# io_board.net
KiCad netlist of a schematic drawn in EAGLE
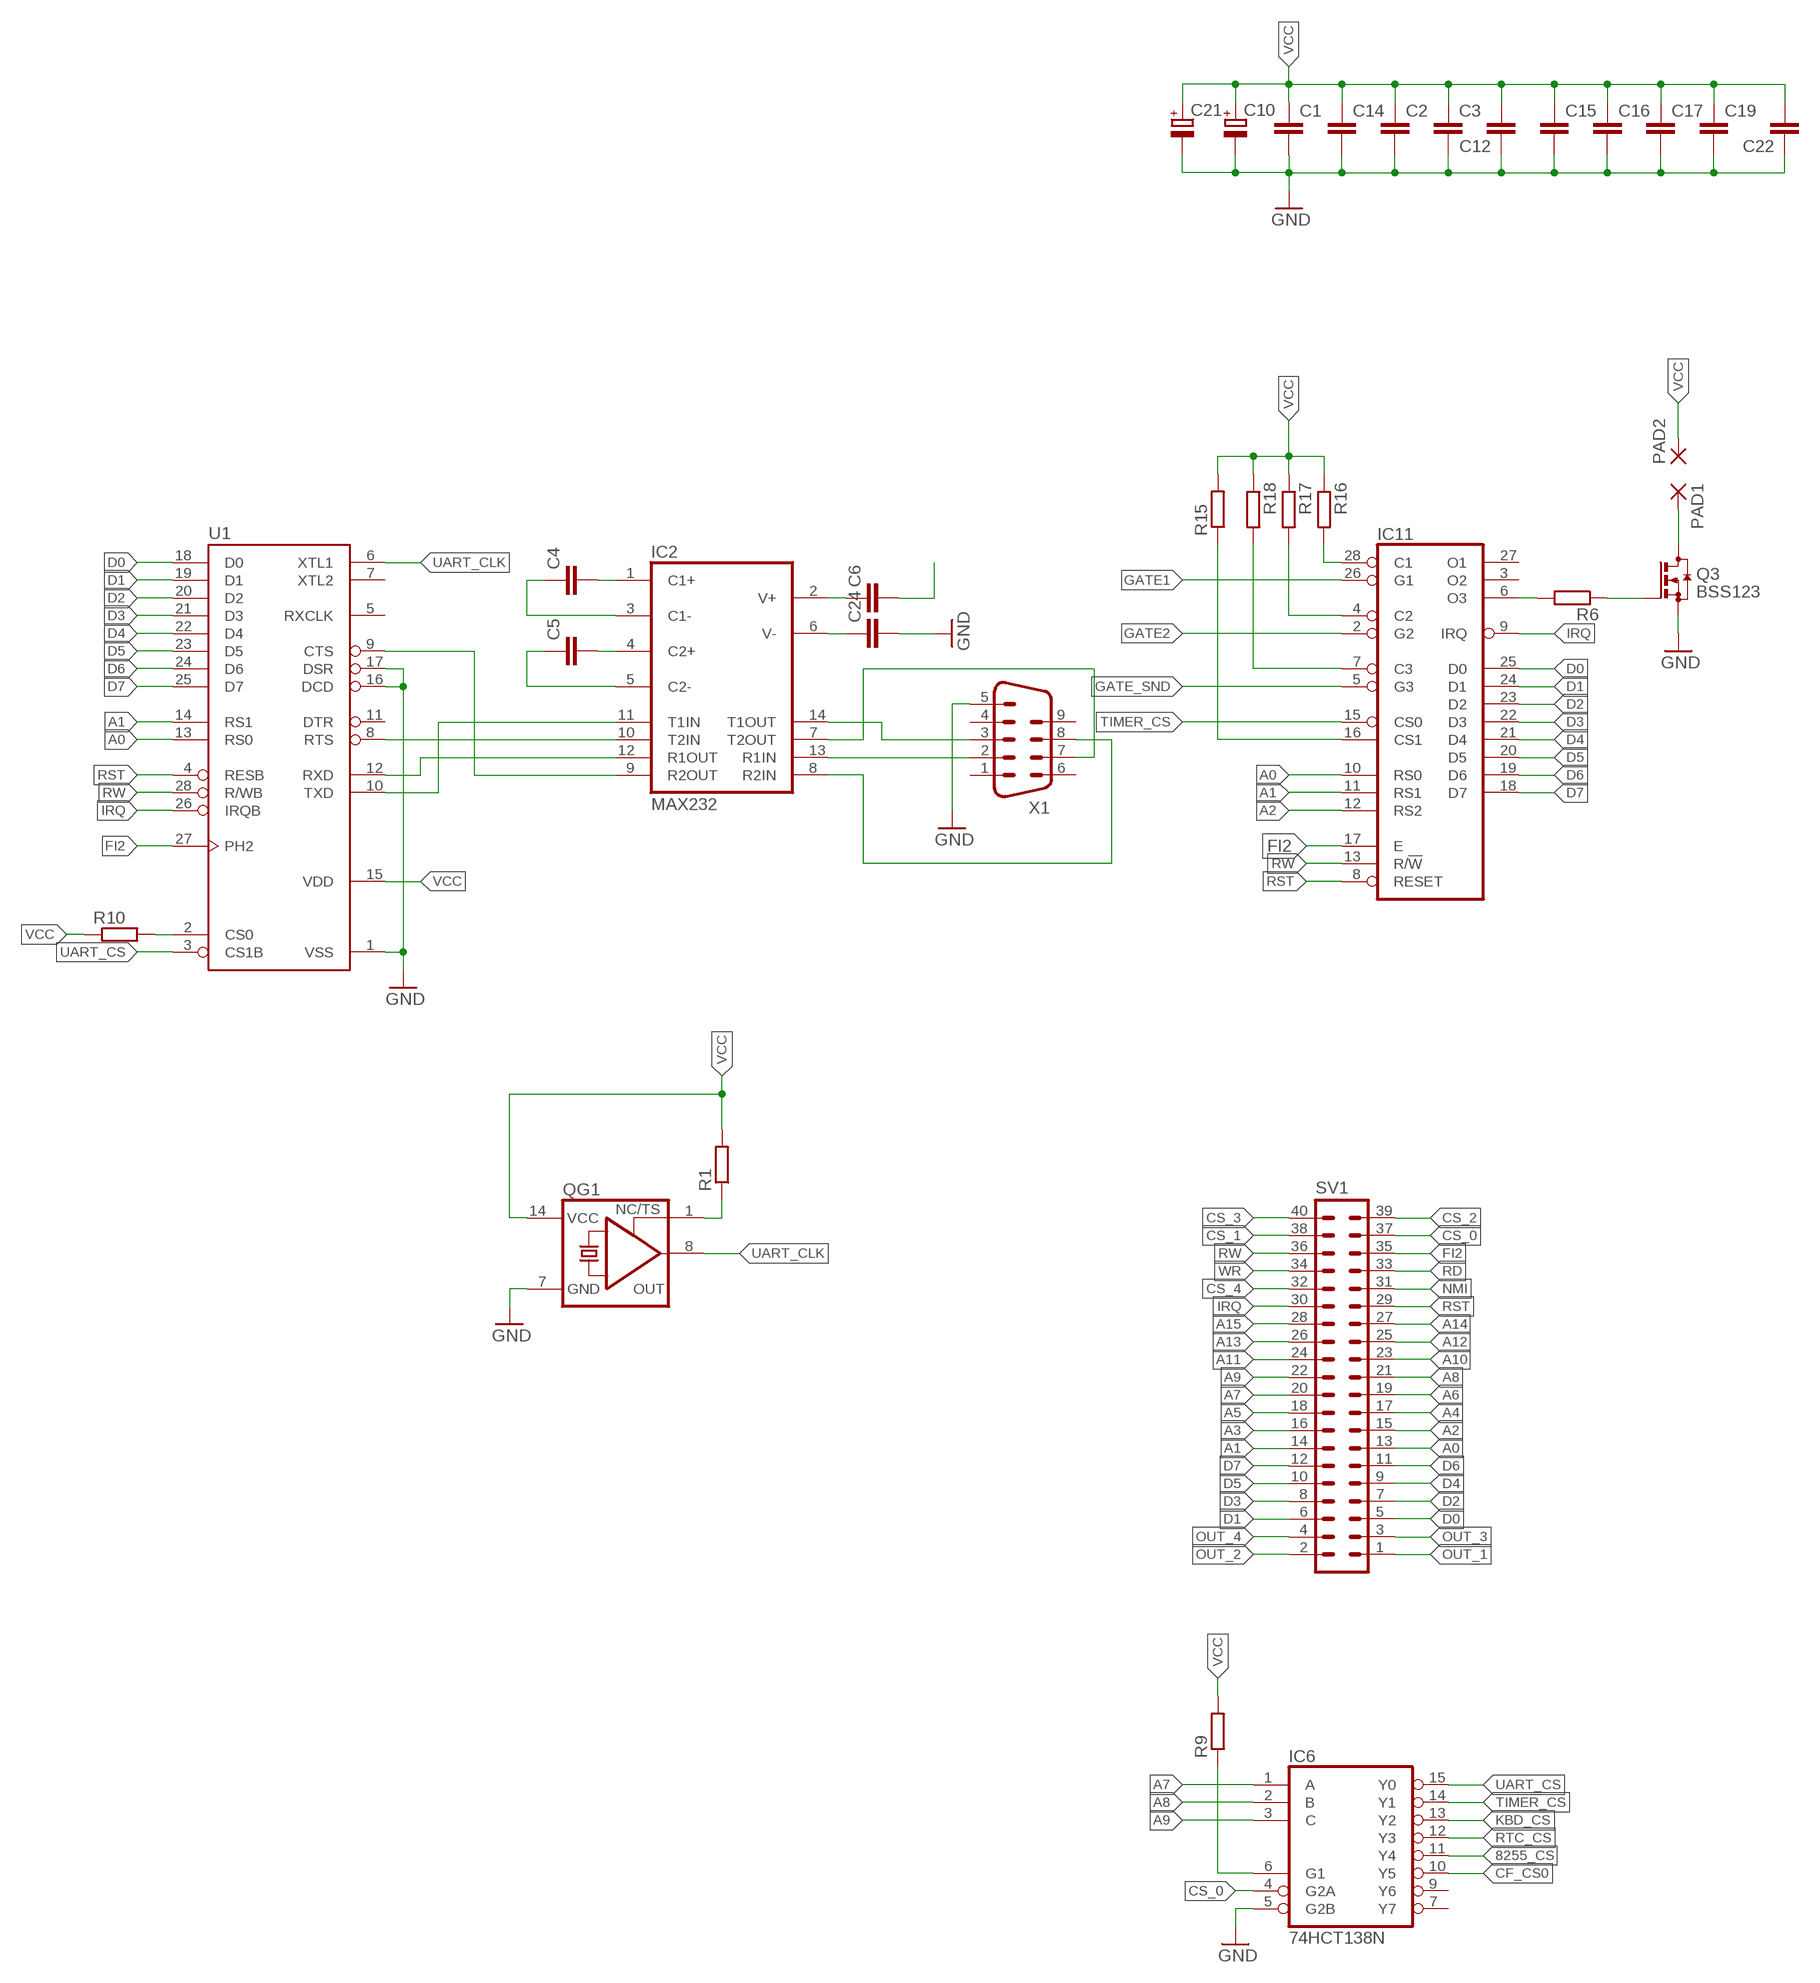
[diagram p0: schematic, sheet 1, part 1 of 2]
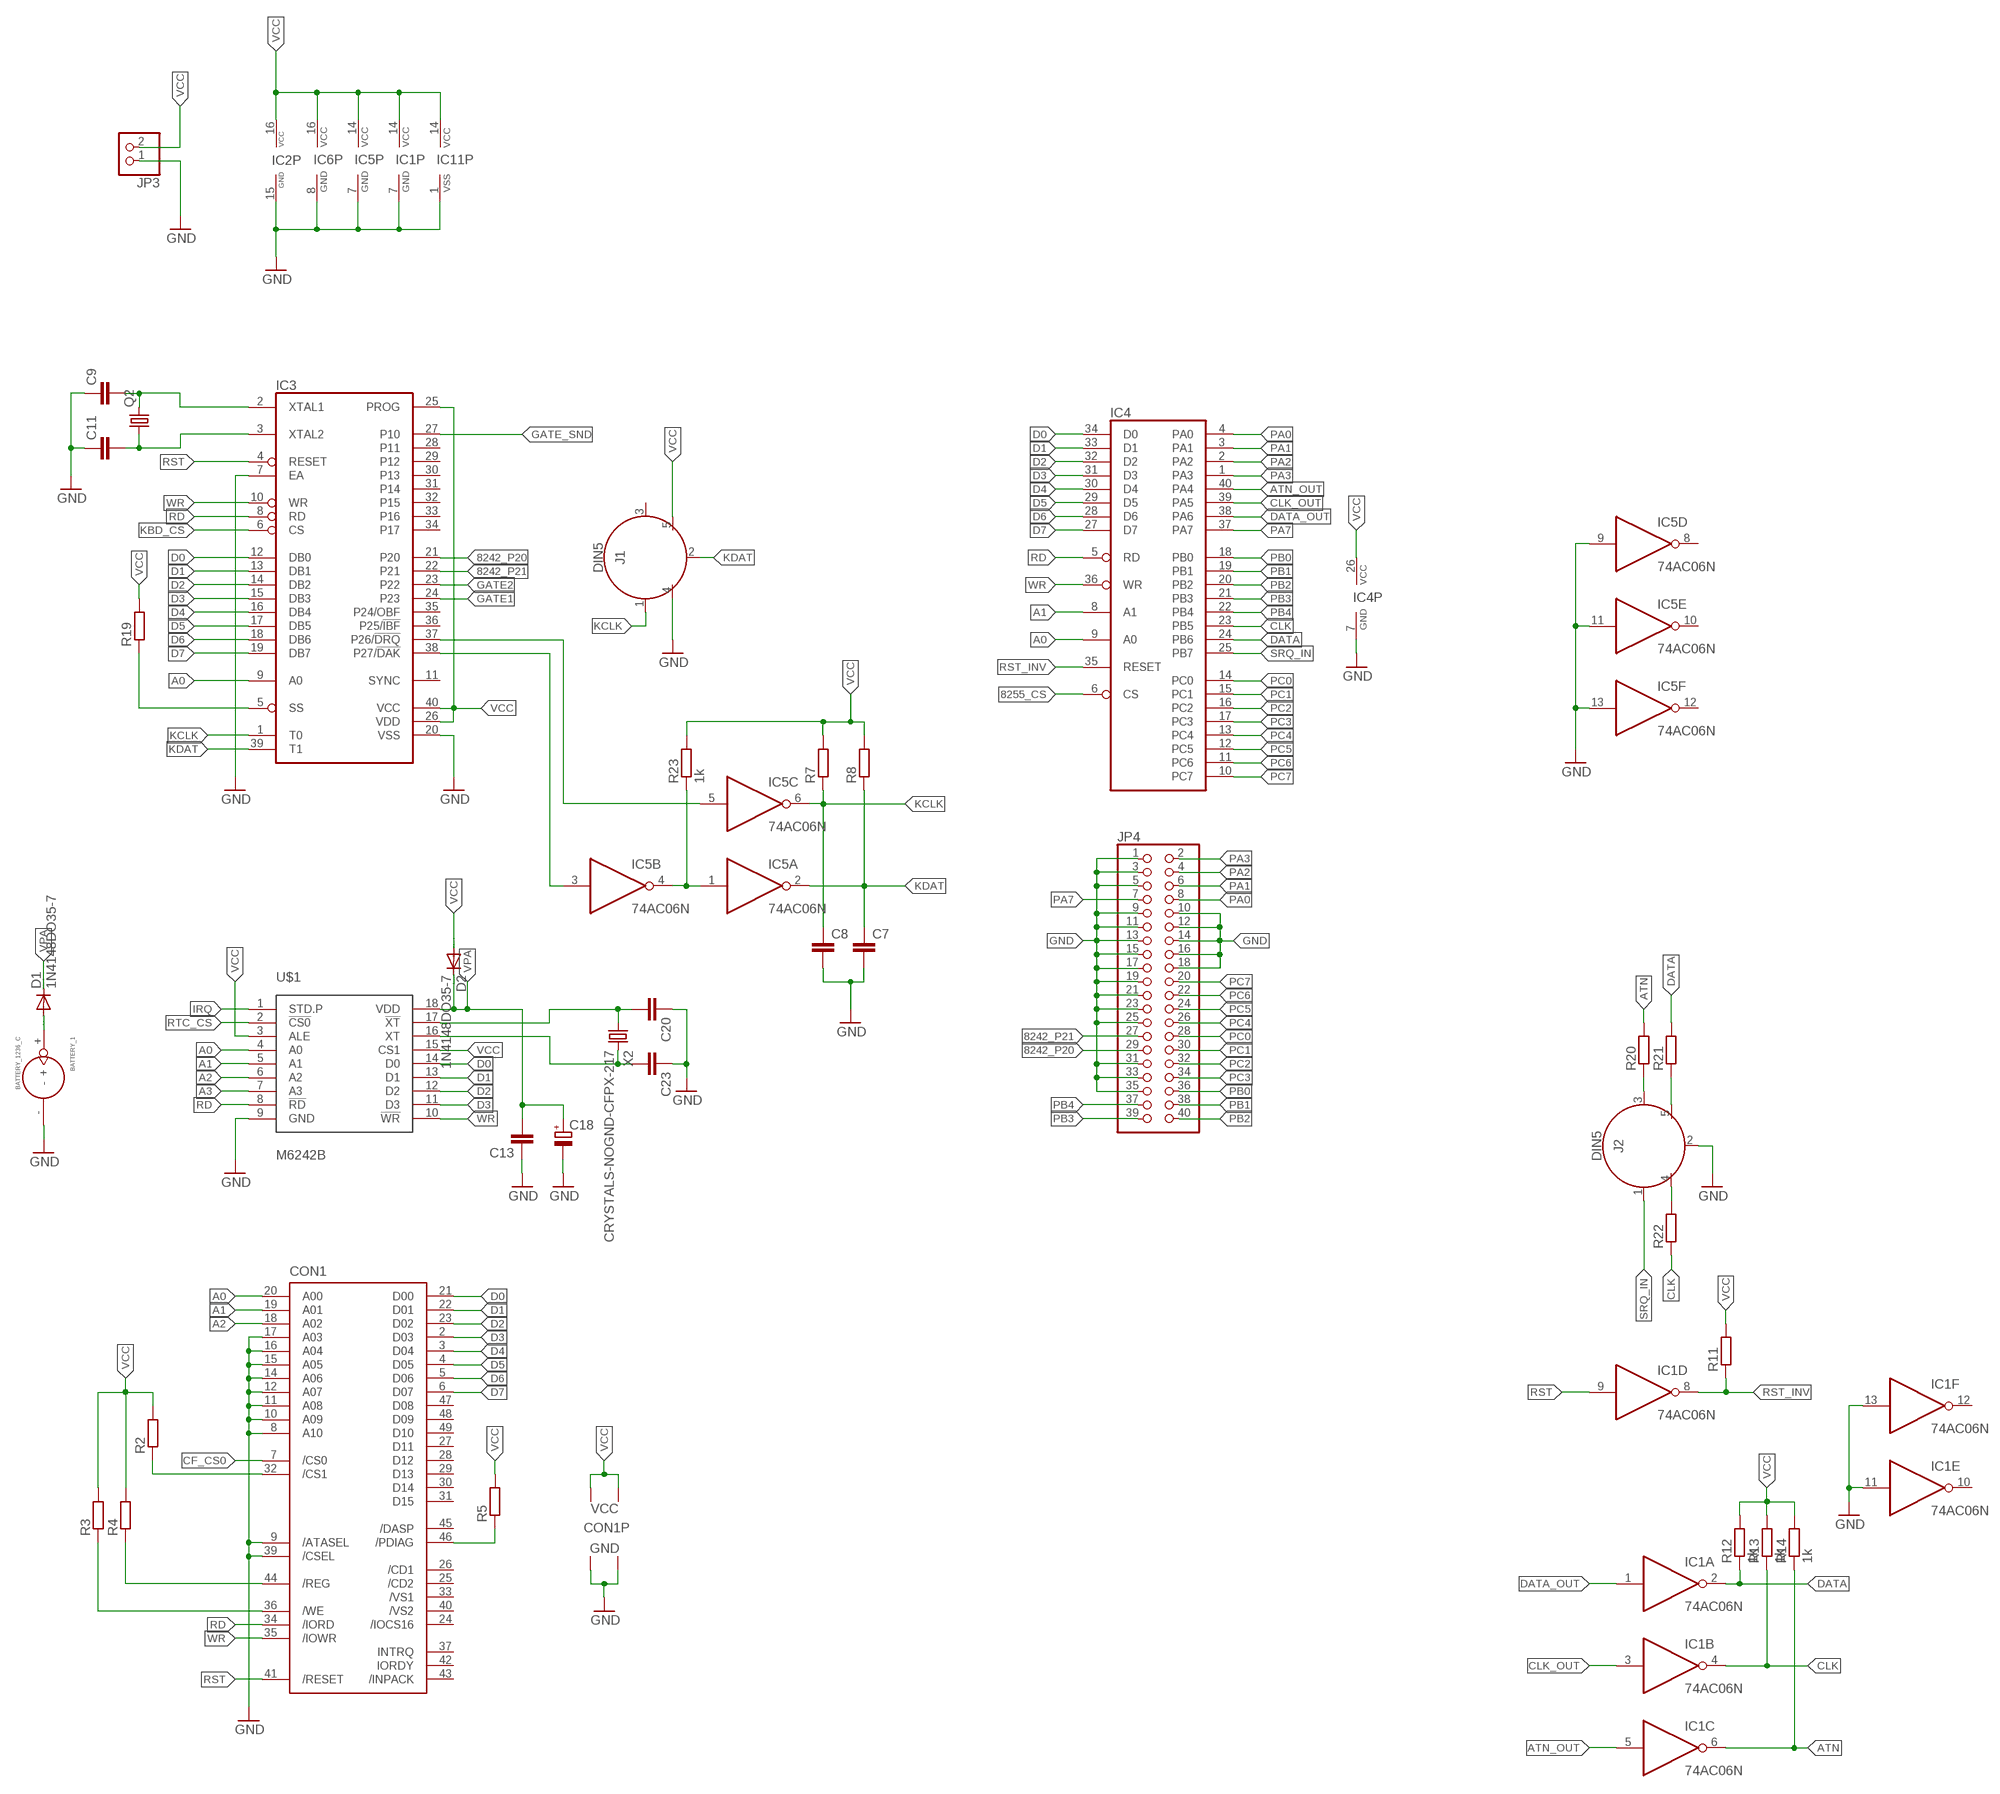
[diagram p1: schematic, sheet 1, part 2 of 2]

(export (version "E")
  (design (tool "Eeschema 10.0.6"))
  (components
    (comp (ref "BATTERY_1")
      (value "BATTERY_1236_C")
      (footprint "eagle-import:BATTERY_1236_C")
      (libsource (lib "eagle-import") (part "BATTERY_1236_C"))
    )
    (comp (ref "C1")
      (value "C-EUC1206")
      (footprint "eagle-import:C1206")
      (libsource (lib "eagle-import") (part "C-EUC1206"))
    )
    (comp (ref "C2")
      (value "C-EUC1206")
      (footprint "eagle-import:C1206")
      (libsource (lib "eagle-import") (part "C-EUC1206"))
    )
    (comp (ref "C3")
      (value "C-EUC1206")
      (footprint "eagle-import:C1206")
      (libsource (lib "eagle-import") (part "C-EUC1206"))
    )
    (comp (ref "C4")
      (value "C-EUC0603")
      (footprint "eagle-import:C0603")
      (libsource (lib "eagle-import") (part "C-EUC0603"))
    )
    (comp (ref "C5")
      (value "C-EUC0603")
      (footprint "eagle-import:C0603")
      (libsource (lib "eagle-import") (part "C-EUC0603"))
    )
    (comp (ref "C6")
      (value "C-EUC0603")
      (footprint "eagle-import:C0603")
      (libsource (lib "eagle-import") (part "C-EUC0603"))
    )
    (comp (ref "C7")
      (value "C-EUC0603")
      (footprint "eagle-import:C0603")
      (libsource (lib "eagle-import") (part "C-EUC0603"))
    )
    (comp (ref "C8")
      (value "C-EUC0603")
      (footprint "eagle-import:C0603")
      (libsource (lib "eagle-import") (part "C-EUC0603"))
    )
    (comp (ref "C9")
      (value "C-EUC0603")
      (footprint "eagle-import:C0603")
      (libsource (lib "eagle-import") (part "C-EUC0603"))
    )
    (comp (ref "C10")
      (value "CPOL-EUE5-10.5")
      (footprint "eagle-import:E5-10,5")
      (libsource (lib "eagle-import") (part "CPOL-EUE5-10.5"))
    )
    (comp (ref "C11")
      (value "C-EUC0603")
      (footprint "eagle-import:C0603")
      (libsource (lib "eagle-import") (part "C-EUC0603"))
    )
    (comp (ref "C12")
      (value "C-EUC0603")
      (footprint "eagle-import:C0603")
      (libsource (lib "eagle-import") (part "C-EUC0603"))
    )
    (comp (ref "C13")
      (value "C-EUC0603")
      (footprint "eagle-import:C0603")
      (libsource (lib "eagle-import") (part "C-EUC0603"))
    )
    (comp (ref "C14")
      (value "C-EUC1206")
      (footprint "eagle-import:C1206")
      (libsource (lib "eagle-import") (part "C-EUC1206"))
    )
    (comp (ref "C15")
      (value "C-EUC1206")
      (footprint "eagle-import:C1206")
      (libsource (lib "eagle-import") (part "C-EUC1206"))
    )
    (comp (ref "C16")
      (value "C-EUC1206")
      (footprint "eagle-import:C1206")
      (libsource (lib "eagle-import") (part "C-EUC1206"))
    )
    (comp (ref "C17")
      (value "C-EUC1206")
      (footprint "eagle-import:C1206")
      (libsource (lib "eagle-import") (part "C-EUC1206"))
    )
    (comp (ref "C18")
      (value "CPOL-EUSMCB")
      (footprint "eagle-import:SMC_B")
      (libsource (lib "eagle-import") (part "CPOL-EUSMCB"))
    )
    (comp (ref "C19")
      (value "C-EUC0603")
      (footprint "eagle-import:C0603")
      (libsource (lib "eagle-import") (part "C-EUC0603"))
    )
    (comp (ref "C20")
      (value "C-EUC0603")
      (footprint "eagle-import:C0603")
      (libsource (lib "eagle-import") (part "C-EUC0603"))
    )
    (comp (ref "C21")
      (value "CPOL-EUSMCB")
      (footprint "eagle-import:SMC_B")
      (libsource (lib "eagle-import") (part "CPOL-EUSMCB"))
    )
    (comp (ref "C22")
      (value "C-EUC0603")
      (footprint "eagle-import:C0603")
      (libsource (lib "eagle-import") (part "C-EUC0603"))
    )
    (comp (ref "C23")
      (value "C-EUC0603")
      (footprint "eagle-import:C0603")
      (libsource (lib "eagle-import") (part "C-EUC0603"))
    )
    (comp (ref "C24")
      (value "C-EUC0603")
      (footprint "eagle-import:C0603")
      (libsource (lib "eagle-import") (part "C-EUC0603"))
    )
    (comp (ref "CON1")
      (value "CF-CARD-IDE_MODE")
      (footprint "eagle-import:MI20-50PD-SF")
      (libsource (lib "eagle-import") (part "CF-CARD-IDE_MODE"))
    )
    (comp (ref "D1")
      (value "1N4148DO35-7")
      (footprint "eagle-import:DO35-7")
      (libsource (lib "eagle-import") (part "1N4148DO35-7"))
    )
    (comp (ref "D2")
      (value "1N4148DO35-7")
      (footprint "eagle-import:DO35-7")
      (libsource (lib "eagle-import") (part "1N4148DO35-7"))
    )
    (comp (ref "IC1")
      (value "74AC06N")
      (footprint "eagle-import:DIL14")
      (libsource (lib "eagle-import") (part "7406NAC"))
    )
    (comp (ref "IC2")
      (value "MAX232")
      (footprint "eagle-import:DIL16")
      (fields (field (name "MF") "MAXIM") (field (name "MPN") "MAX232ACPE+"))
      (libsource (lib "eagle-import") (part "MAX232"))
    )
    (comp (ref "IC3")
      (value "UPI-8042AH")
      (footprint "eagle-import:DIL40")
      (libsource (lib "eagle-import") (part "UPI-8042AH"))
    )
    (comp (ref "IC4")
      (value "8255A")
      (footprint "eagle-import:DIL40")
      (libsource (lib "eagle-import") (part "8255A"))
    )
    (comp (ref "IC5")
      (value "74AC06N")
      (footprint "eagle-import:DIL14")
      (libsource (lib "eagle-import") (part "7406NAC"))
    )
    (comp (ref "IC6")
      (value "74HCT138N")
      (footprint "eagle-import:DIL16")
      (libsource (lib "eagle-import") (part "74138NHCT"))
    )
    (comp (ref "IC11")
      (value "6840")
      (footprint "eagle-import:DIL28")
      (libsource (lib "eagle-import") (part "6840"))
    )
    (comp (ref "J1")
      (value "DIN5")
      (footprint "eagle-import:DIN5-RA-PTH")
      (libsource (lib "eagle-import") (part "DIN5"))
    )
    (comp (ref "J2")
      (value "DIN5")
      (footprint "eagle-import:DIN5-RA-PTH")
      (libsource (lib "eagle-import") (part "DIN5"))
    )
    (comp (ref "JP3")
      (value "PINHD-1X2/90")
      (footprint "eagle-import:1X02_90")
      (libsource (lib "eagle-import") (part "PINHD-1X2/90"))
    )
    (comp (ref "JP4")
      (value "PINHD-2X20")
      (footprint "eagle-import:2X20")
      (libsource (lib "eagle-import") (part "PINHD-2X20"))
    )
    (comp (ref "PAD1")
      (value "2,15/1,0")
      (footprint "eagle-import:2,15_1,0")
      (libsource (lib "eagle-import") (part "2,15/1,0"))
    )
    (comp (ref "PAD2")
      (value "2,15/1,0")
      (footprint "eagle-import:2,15_1,0")
      (libsource (lib "eagle-import") (part "2,15/1,0"))
    )
    (comp (ref "Q2")
      (value "CRYSTALHC49S")
      (footprint "eagle-import:HC49_S")
      (libsource (lib "eagle-import") (part "CRYSTALHC49S"))
    )
    (comp (ref "Q3")
      (value "BSS123")
      (footprint "eagle-import:SOT23")
      (libsource (lib "eagle-import") (part "BSS123"))
    )
    (comp (ref "QG1")
      (value "XO-14")
      (footprint "eagle-import:DIL14S")
      (libsource (lib "eagle-import") (part "XO-14"))
    )
    (comp (ref "R1")
      (value "R-EU_R1206")
      (footprint "eagle-import:R1206")
      (libsource (lib "eagle-import") (part "R-EU_R1206"))
    )
    (comp (ref "R2")
      (value "R-EU_R0603")
      (footprint "eagle-import:R0603")
      (libsource (lib "eagle-import") (part "R-EU_R0603"))
    )
    (comp (ref "R3")
      (value "R-EU_R0603")
      (footprint "eagle-import:R0603")
      (libsource (lib "eagle-import") (part "R-EU_R0603"))
    )
    (comp (ref "R4")
      (value "R-EU_R0603")
      (footprint "eagle-import:R0603")
      (libsource (lib "eagle-import") (part "R-EU_R0603"))
    )
    (comp (ref "R5")
      (value "R-EU_R0603")
      (footprint "eagle-import:R0603")
      (libsource (lib "eagle-import") (part "R-EU_R0603"))
    )
    (comp (ref "R6")
      (value "R-EU_R0603")
      (footprint "eagle-import:R0603")
      (libsource (lib "eagle-import") (part "R-EU_R0603"))
    )
    (comp (ref "R7")
      (value "R-EU_R0603")
      (footprint "eagle-import:R0603")
      (libsource (lib "eagle-import") (part "R-EU_R0603"))
    )
    (comp (ref "R8")
      (value "R-EU_R0603")
      (footprint "eagle-import:R0603")
      (libsource (lib "eagle-import") (part "R-EU_R0603"))
    )
    (comp (ref "R9")
      (value "R-EU_R1206")
      (footprint "eagle-import:R1206")
      (libsource (lib "eagle-import") (part "R-EU_R1206"))
    )
    (comp (ref "R10")
      (value "R-EU_R0603")
      (footprint "eagle-import:R0603")
      (libsource (lib "eagle-import") (part "R-EU_R0603"))
    )
    (comp (ref "R11")
      (value "R-EU_R0603")
      (footprint "eagle-import:R0603")
      (libsource (lib "eagle-import") (part "R-EU_R0603"))
    )
    (comp (ref "R12")
      (value "1k")
      (footprint "eagle-import:0204_7")
      (libsource (lib "eagle-import") (part "R-EU_0204/7"))
    )
    (comp (ref "R13")
      (value "1k")
      (footprint "eagle-import:0204_5")
      (libsource (lib "eagle-import") (part "R-EU_0204/5"))
    )
    (comp (ref "R14")
      (value "1k")
      (footprint "eagle-import:0204_7")
      (libsource (lib "eagle-import") (part "R-EU_0204/7"))
    )
    (comp (ref "R15")
      (value "R-EU_R0603")
      (footprint "eagle-import:R0603")
      (libsource (lib "eagle-import") (part "R-EU_R0603"))
    )
    (comp (ref "R16")
      (value "R-EU_0204/5")
      (footprint "eagle-import:0204_5")
      (libsource (lib "eagle-import") (part "R-EU_0204/5"))
    )
    (comp (ref "R17")
      (value "R-EU_R0603")
      (footprint "eagle-import:R0603")
      (libsource (lib "eagle-import") (part "R-EU_R0603"))
    )
    (comp (ref "R18")
      (value "R-EU_R0603")
      (footprint "eagle-import:R0603")
      (libsource (lib "eagle-import") (part "R-EU_R0603"))
    )
    (comp (ref "R19")
      (value "R-EU_0204/5")
      (footprint "eagle-import:0204_5")
      (libsource (lib "eagle-import") (part "R-EU_0204/5"))
    )
    (comp (ref "R20")
      (value "R-EU_R0805")
      (footprint "eagle-import:R0805")
      (libsource (lib "eagle-import") (part "R-EU_R0805"))
    )
    (comp (ref "R21")
      (value "R-EU_R0805")
      (footprint "eagle-import:R0805")
      (libsource (lib "eagle-import") (part "R-EU_R0805"))
    )
    (comp (ref "R22")
      (value "R-EU_R0805")
      (footprint "eagle-import:R0805")
      (libsource (lib "eagle-import") (part "R-EU_R0805"))
    )
    (comp (ref "R23")
      (value "1k")
      (footprint "eagle-import:0204_7")
      (libsource (lib "eagle-import") (part "R-EU_0204/7"))
    )
    (comp (ref "SV1")
      (value "ML40L")
      (footprint "eagle-import:ML40L")
      (libsource (lib "eagle-import") (part "ML40L"))
    )
    (comp (ref "U$1")
      (value "M6242B")
      (footprint "eagle-import:DIL18")
      (libsource (lib "eagle-import") (part "M6242B"))
    )
    (comp (ref "U1")
      (value "G65SC51P")
      (footprint "eagle-import:DIP-28")
      (libsource (lib "eagle-import") (part "G65SC51P"))
    )
    (comp (ref "X1")
      (value "M09HP")
      (footprint "eagle-import:M09HP")
      (libsource (lib "eagle-import") (part "M09HP"))
    )
    (comp (ref "X2")
      (value "CRYSTALS-NOGND-CFPX-217")
      (footprint "eagle-import:3.2X1.5-2-PAD")
      (libsource (lib "eagle-import") (part "CRYSTALS-NOGND-CFPX-217"))
    )
  )
  (nets
    (net (code "1") (name "8242_P20") (class "Default")
      (node (ref "IC3") (pin "21") (pinfunction "P20_21") (pintype "bidirectional"))
      (node (ref "JP4") (pin "29") (pinfunction "29_29") (pintype "passive"))
    )
    (net (code "2") (name "8242_P21") (class "Default")
      (node (ref "IC3") (pin "22") (pinfunction "P21_22") (pintype "bidirectional"))
      (node (ref "JP4") (pin "27") (pinfunction "27_27") (pintype "passive"))
    )
    (net (code "3") (name "8255_CS") (class "Default")
      (node (ref "IC4") (pin "6") (pinfunction "CS_6") (pintype "input"))
      (node (ref "IC6") (pin "11") (pinfunction "Y4_11") (pintype "output"))
    )
    (net (code "4") (name "A0") (class "Default")
      (node (ref "CON1") (pin "20") (pinfunction "A00_20") (pintype "input"))
      (node (ref "IC11") (pin "10") (pinfunction "RS0_10") (pintype "input"))
      (node (ref "IC3") (pin "9") (pinfunction "A0_9") (pintype "input"))
      (node (ref "IC4") (pin "9") (pinfunction "A0_9") (pintype "input"))
      (node (ref "SV1") (pin "13") (pinfunction "13_13") (pintype "passive"))
      (node (ref "U$1") (pin "4") (pinfunction "A0_4") (pintype "bidirectional"))
      (node (ref "U1") (pin "13") (pinfunction "RS0_13") (pintype "input"))
    )
    (net (code "5") (name "A1") (class "Default")
      (node (ref "CON1") (pin "19") (pinfunction "A01_19") (pintype "input"))
      (node (ref "IC11") (pin "11") (pinfunction "RS1_11") (pintype "input"))
      (node (ref "IC4") (pin "8") (pinfunction "A1_8") (pintype "input"))
      (node (ref "SV1") (pin "14") (pinfunction "14_14") (pintype "passive"))
      (node (ref "U$1") (pin "5") (pinfunction "A1_5") (pintype "bidirectional"))
      (node (ref "U1") (pin "14") (pinfunction "RS1_14") (pintype "input"))
    )
    (net (code "6") (name "A2") (class "Default")
      (node (ref "CON1") (pin "18") (pinfunction "A02_18") (pintype "input"))
      (node (ref "IC11") (pin "12") (pinfunction "RS2_12") (pintype "input"))
      (node (ref "SV1") (pin "15") (pinfunction "15_15") (pintype "passive"))
      (node (ref "U$1") (pin "6") (pinfunction "A2_6") (pintype "bidirectional"))
    )
    (net (code "7") (name "A3") (class "Default")
      (node (ref "SV1") (pin "16") (pinfunction "16_16") (pintype "passive"))
      (node (ref "U$1") (pin "7") (pinfunction "A3_7") (pintype "bidirectional"))
    )
    (net (code "8") (name "A4") (class "Default")
      (node (ref "SV1") (pin "17") (pinfunction "17_17") (pintype "passive"))
    )
    (net (code "9") (name "A5") (class "Default")
      (node (ref "SV1") (pin "18") (pinfunction "18_18") (pintype "passive"))
    )
    (net (code "10") (name "A6") (class "Default")
      (node (ref "SV1") (pin "19") (pinfunction "19_19") (pintype "passive"))
    )
    (net (code "11") (name "A7") (class "Default")
      (node (ref "IC6") (pin "1") (pinfunction "A_1") (pintype "input"))
      (node (ref "SV1") (pin "20") (pinfunction "20_20") (pintype "passive"))
    )
    (net (code "12") (name "A8") (class "Default")
      (node (ref "IC6") (pin "2") (pinfunction "B_2") (pintype "input"))
      (node (ref "SV1") (pin "21") (pinfunction "21_21") (pintype "passive"))
    )
    (net (code "13") (name "A9") (class "Default")
      (node (ref "IC6") (pin "3") (pinfunction "C_3") (pintype "input"))
      (node (ref "SV1") (pin "22") (pinfunction "22_22") (pintype "passive"))
    )
    (net (code "14") (name "A10") (class "Default")
      (node (ref "SV1") (pin "23") (pinfunction "23_23") (pintype "passive"))
    )
    (net (code "15") (name "A11") (class "Default")
      (node (ref "SV1") (pin "24") (pinfunction "24_24") (pintype "passive"))
    )
    (net (code "16") (name "A12") (class "Default")
      (node (ref "SV1") (pin "25") (pinfunction "25_25") (pintype "passive"))
    )
    (net (code "17") (name "A13") (class "Default")
      (node (ref "SV1") (pin "26") (pinfunction "26_26") (pintype "passive"))
    )
    (net (code "18") (name "A14") (class "Default")
      (node (ref "SV1") (pin "27") (pinfunction "27_27") (pintype "passive"))
    )
    (net (code "19") (name "A15") (class "Default")
      (node (ref "SV1") (pin "28") (pinfunction "28_28") (pintype "passive"))
    )
    (net (code "20") (name "ATN") (class "Default")
      (node (ref "IC1") (pin "6") (pinfunction "O_6") (pintype "open_collector"))
      (node (ref "R14") (pin "1") (pinfunction "1_1") (pintype "passive"))
      (node (ref "R20") (pin "2") (pinfunction "2_2") (pintype "passive"))
    )
    (net (code "21") (name "ATN_OUT") (class "Default")
      (node (ref "IC1") (pin "5") (pinfunction "I_5") (pintype "input"))
      (node (ref "IC4") (pin "40") (pinfunction "PA4_40") (pintype "bidirectional"))
    )
    (net (code "22") (name "CF_CS0") (class "Default")
      (node (ref "CON1") (pin "7") (pinfunction "/CS0_7") (pintype "input"))
      (node (ref "IC6") (pin "10") (pinfunction "Y5_10") (pintype "output"))
    )
    (net (code "23") (name "CLK") (class "Default")
      (node (ref "IC1") (pin "4") (pinfunction "O_4") (pintype "open_collector"))
      (node (ref "IC4") (pin "23") (pinfunction "PB5_23") (pintype "bidirectional"))
      (node (ref "R13") (pin "1") (pinfunction "1_1") (pintype "passive"))
      (node (ref "R22") (pin "1") (pinfunction "1_1") (pintype "passive"))
    )
    (net (code "24") (name "CLK_OUT") (class "Default")
      (node (ref "IC1") (pin "3") (pinfunction "I_3") (pintype "input"))
      (node (ref "IC4") (pin "39") (pinfunction "PA5_39") (pintype "bidirectional"))
    )
    (net (code "25") (name "CS_0") (class "Default")
      (node (ref "IC6") (pin "4") (pinfunction "G2A_4") (pintype "input"))
      (node (ref "SV1") (pin "37") (pinfunction "37_37") (pintype "passive"))
    )
    (net (code "26") (name "CS_1") (class "Default")
      (node (ref "SV1") (pin "38") (pinfunction "38_38") (pintype "passive"))
    )
    (net (code "27") (name "CS_2") (class "Default")
      (node (ref "SV1") (pin "39") (pinfunction "39_39") (pintype "passive"))
    )
    (net (code "28") (name "CS_3") (class "Default")
      (node (ref "SV1") (pin "40") (pinfunction "40_40") (pintype "passive"))
    )
    (net (code "29") (name "CS_4") (class "Default")
      (node (ref "SV1") (pin "32") (pinfunction "32_32") (pintype "passive"))
    )
    (net (code "30") (name "D0") (class "Default")
      (node (ref "CON1") (pin "21") (pinfunction "D00_21") (pintype "bidirectional"))
      (node (ref "IC11") (pin "25") (pinfunction "D0_25") (pintype "bidirectional"))
      (node (ref "IC3") (pin "12") (pinfunction "DB0_12") (pintype "bidirectional"))
      (node (ref "IC4") (pin "34") (pinfunction "D0_34") (pintype "bidirectional"))
      (node (ref "SV1") (pin "5") (pinfunction "5_5") (pintype "passive"))
      (node (ref "U$1") (pin "14") (pinfunction "D0_14") (pintype "bidirectional"))
      (node (ref "U1") (pin "18") (pinfunction "D0_18") (pintype "bidirectional"))
    )
    (net (code "31") (name "D1") (class "Default")
      (node (ref "CON1") (pin "22") (pinfunction "D01_22") (pintype "bidirectional"))
      (node (ref "IC11") (pin "24") (pinfunction "D1_24") (pintype "bidirectional"))
      (node (ref "IC3") (pin "13") (pinfunction "DB1_13") (pintype "bidirectional"))
      (node (ref "IC4") (pin "33") (pinfunction "D1_33") (pintype "bidirectional"))
      (node (ref "SV1") (pin "6") (pinfunction "6_6") (pintype "passive"))
      (node (ref "U$1") (pin "13") (pinfunction "D1_13") (pintype "bidirectional"))
      (node (ref "U1") (pin "19") (pinfunction "D1_19") (pintype "bidirectional"))
    )
    (net (code "32") (name "D2") (class "Default")
      (node (ref "CON1") (pin "23") (pinfunction "D02_23") (pintype "bidirectional"))
      (node (ref "IC11") (pin "23") (pinfunction "D2_23") (pintype "bidirectional"))
      (node (ref "IC3") (pin "14") (pinfunction "DB2_14") (pintype "bidirectional"))
      (node (ref "IC4") (pin "32") (pinfunction "D2_32") (pintype "bidirectional"))
      (node (ref "SV1") (pin "7") (pinfunction "7_7") (pintype "passive"))
      (node (ref "U$1") (pin "12") (pinfunction "D2_12") (pintype "bidirectional"))
      (node (ref "U1") (pin "20") (pinfunction "D2_20") (pintype "bidirectional"))
    )
    (net (code "33") (name "D3") (class "Default")
      (node (ref "CON1") (pin "2") (pinfunction "D03_2") (pintype "bidirectional"))
      (node (ref "IC11") (pin "22") (pinfunction "D3_22") (pintype "bidirectional"))
      (node (ref "IC3") (pin "15") (pinfunction "DB3_15") (pintype "bidirectional"))
      (node (ref "IC4") (pin "31") (pinfunction "D3_31") (pintype "bidirectional"))
      (node (ref "SV1") (pin "8") (pinfunction "8_8") (pintype "passive"))
      (node (ref "U$1") (pin "11") (pinfunction "D3_11") (pintype "bidirectional"))
      (node (ref "U1") (pin "21") (pinfunction "D3_21") (pintype "bidirectional"))
    )
    (net (code "34") (name "D4") (class "Default")
      (node (ref "CON1") (pin "3") (pinfunction "D04_3") (pintype "bidirectional"))
      (node (ref "IC11") (pin "21") (pinfunction "D4_21") (pintype "bidirectional"))
      (node (ref "IC3") (pin "16") (pinfunction "DB4_16") (pintype "bidirectional"))
      (node (ref "IC4") (pin "30") (pinfunction "D4_30") (pintype "bidirectional"))
      (node (ref "SV1") (pin "9") (pinfunction "9_9") (pintype "passive"))
      (node (ref "U1") (pin "22") (pinfunction "D4_22") (pintype "bidirectional"))
    )
    (net (code "35") (name "D5") (class "Default")
      (node (ref "CON1") (pin "4") (pinfunction "D05_4") (pintype "bidirectional"))
      (node (ref "IC11") (pin "20") (pinfunction "D5_20") (pintype "bidirectional"))
      (node (ref "IC3") (pin "17") (pinfunction "DB5_17") (pintype "bidirectional"))
      (node (ref "IC4") (pin "29") (pinfunction "D5_29") (pintype "bidirectional"))
      (node (ref "SV1") (pin "10") (pinfunction "10_10") (pintype "passive"))
      (node (ref "U1") (pin "23") (pinfunction "D5_23") (pintype "bidirectional"))
    )
    (net (code "36") (name "D6") (class "Default")
      (node (ref "CON1") (pin "5") (pinfunction "D06_5") (pintype "bidirectional"))
      (node (ref "IC11") (pin "19") (pinfunction "D6_19") (pintype "bidirectional"))
      (node (ref "IC3") (pin "18") (pinfunction "DB6_18") (pintype "bidirectional"))
      (node (ref "IC4") (pin "28") (pinfunction "D6_28") (pintype "bidirectional"))
      (node (ref "SV1") (pin "11") (pinfunction "11_11") (pintype "passive"))
      (node (ref "U1") (pin "24") (pinfunction "D6_24") (pintype "bidirectional"))
    )
    (net (code "37") (name "D7") (class "Default")
      (node (ref "CON1") (pin "6") (pinfunction "D07_6") (pintype "bidirectional"))
      (node (ref "IC11") (pin "18") (pinfunction "D7_18") (pintype "bidirectional"))
      (node (ref "IC3") (pin "19") (pinfunction "DB7_19") (pintype "bidirectional"))
      (node (ref "IC4") (pin "27") (pinfunction "D7_27") (pintype "bidirectional"))
      (node (ref "SV1") (pin "12") (pinfunction "12_12") (pintype "passive"))
      (node (ref "U1") (pin "25") (pinfunction "D7_25") (pintype "bidirectional"))
    )
    (net (code "38") (name "DATA") (class "Default")
      (node (ref "IC1") (pin "2") (pinfunction "O_2") (pintype "open_collector"))
      (node (ref "IC4") (pin "24") (pinfunction "PB6_24") (pintype "bidirectional"))
      (node (ref "R12") (pin "1") (pinfunction "1_1") (pintype "passive"))
      (node (ref "R21") (pin "2") (pinfunction "2_2") (pintype "passive"))
    )
    (net (code "39") (name "DATA_OUT") (class "Default")
      (node (ref "IC1") (pin "1") (pinfunction "I_1") (pintype "input"))
      (node (ref "IC4") (pin "38") (pinfunction "PA6_38") (pintype "bidirectional"))
    )
    (net (code "40") (name "FI2") (class "Default")
      (node (ref "IC11") (pin "17") (pinfunction "E_17") (pintype "input"))
      (node (ref "SV1") (pin "35") (pinfunction "35_35") (pintype "passive"))
      (node (ref "U1") (pin "27") (pinfunction "PH2_27") (pintype "power_in"))
    )
    (net (code "41") (name "GATE1") (class "Default")
      (node (ref "IC11") (pin "26") (pinfunction "G1_26") (pintype "input"))
      (node (ref "IC3") (pin "24") (pinfunction "P23_24") (pintype "bidirectional"))
    )
    (net (code "42") (name "GATE2") (class "Default")
      (node (ref "IC11") (pin "2") (pinfunction "G2_2") (pintype "input"))
      (node (ref "IC3") (pin "23") (pinfunction "P22_23") (pintype "bidirectional"))
    )
    (net (code "43") (name "GATE_SND") (class "Default")
      (node (ref "IC11") (pin "5") (pinfunction "G3_5") (pintype "input"))
      (node (ref "IC3") (pin "27") (pinfunction "P10_27") (pintype "bidirectional"))
    )
    (net (code "44") (name "GND") (class "Default")
      (node (ref "BATTERY_1") (pin "-") (pinfunction "-_-") (pintype "bidirectional"))
      (node (ref "C1") (pin "2") (pinfunction "2_2") (pintype "passive"))
      (node (ref "C10") (pin "-") (pinfunction "-_-") (pintype "passive"))
      (node (ref "C11") (pin "1") (pinfunction "1_1") (pintype "passive"))
      (node (ref "C12") (pin "1") (pinfunction "1_1") (pintype "passive"))
      (node (ref "C13") (pin "1") (pinfunction "1_1") (pintype "passive"))
      (node (ref "C14") (pin "2") (pinfunction "2_2") (pintype "passive"))
      (node (ref "C15") (pin "2") (pinfunction "2_2") (pintype "passive"))
      (node (ref "C16") (pin "2") (pinfunction "2_2") (pintype "passive"))
      (node (ref "C17") (pin "2") (pinfunction "2_2") (pintype "passive"))
      (node (ref "C18") (pin "-") (pinfunction "-_-") (pintype "passive"))
      (node (ref "C19") (pin "2") (pinfunction "2_2") (pintype "passive"))
      (node (ref "C2") (pin "2") (pinfunction "2_2") (pintype "passive"))
      (node (ref "C20") (pin "1") (pinfunction "1_1") (pintype "passive"))
      (node (ref "C21") (pin "-") (pinfunction "-_-") (pintype "passive"))
      (node (ref "C22") (pin "1") (pinfunction "1_1") (pintype "passive"))
      (node (ref "C23") (pin "1") (pinfunction "1_1") (pintype "passive"))
      (node (ref "C24") (pin "2") (pinfunction "2_2") (pintype "passive"))
      (node (ref "C3") (pin "2") (pinfunction "2_2") (pintype "passive"))
      (node (ref "C7") (pin "2") (pinfunction "2_2") (pintype "passive"))
      (node (ref "C8") (pin "2") (pinfunction "2_2") (pintype "passive"))
      (node (ref "C9") (pin "1") (pinfunction "1_1") (pintype "passive"))
      (node (ref "CON1") (pin "1") (pinfunction "GND1_1") (pintype "power_in"))
      (node (ref "CON1") (pin "10") (pinfunction "A09_10") (pintype "input"))
      (node (ref "CON1") (pin "11") (pinfunction "A08_11") (pintype "input"))
      (node (ref "CON1") (pin "12") (pinfunction "A07_12") (pintype "input"))
      (node (ref "CON1") (pin "14") (pinfunction "A06_14") (pintype "input"))
      (node (ref "CON1") (pin "15") (pinfunction "A05_15") (pintype "input"))
      (node (ref "CON1") (pin "16") (pinfunction "A04_16") (pintype "input"))
      (node (ref "CON1") (pin "17") (pinfunction "A03_17") (pintype "input"))
      (node (ref "CON1") (pin "39") (pinfunction "/CSEL_39") (pintype "input"))
      (node (ref "CON1") (pin "50") (pinfunction "GND2_50") (pintype "power_in"))
      (node (ref "CON1") (pin "8") (pinfunction "A10_8") (pintype "input"))
      (node (ref "CON1") (pin "9") (pinfunction "/ATASEL_9") (pintype "input"))
      (node (ref "IC1") (pin "11") (pinfunction "I_11") (pintype "input"))
      (node (ref "IC1") (pin "13") (pinfunction "I_13") (pintype "input"))
      (node (ref "IC1") (pin "7") (pinfunction "GND_7") (pintype "power_in"))
      (node (ref "IC11") (pin "1") (pinfunction "VSS_1") (pintype "power_in"))
      (node (ref "IC2") (pin "15") (pinfunction "GND_15") (pintype "power_in"))
      (node (ref "IC3") (pin "20") (pinfunction "VSS_20") (pintype "power_in"))
      (node (ref "IC3") (pin "7") (pinfunction "EA_7") (pintype "input"))
      (node (ref "IC4") (pin "7") (pinfunction "GND_7") (pintype "power_in"))
      (node (ref "IC5") (pin "11") (pinfunction "I_11") (pintype "input"))
      (node (ref "IC5") (pin "13") (pinfunction "I_13") (pintype "input"))
      (node (ref "IC5") (pin "7") (pinfunction "GND_7") (pintype "power_in"))
      (node (ref "IC5") (pin "9") (pinfunction "I_9") (pintype "input"))
      (node (ref "IC6") (pin "5") (pinfunction "G2B_5") (pintype "input"))
      (node (ref "IC6") (pin "8") (pinfunction "GND_8") (pintype "power_in"))
      (node (ref "J1") (pin "4") (pinfunction "4_4") (pintype "bidirectional"))
      (node (ref "J2") (pin "2") (pinfunction "2_2") (pintype "bidirectional"))
      (node (ref "JP3") (pin "1") (pinfunction "1_1") (pintype "passive"))
      (node (ref "JP4") (pin "1") (pinfunction "1_1") (pintype "passive"))
      (node (ref "JP4") (pin "10") (pinfunction "10_10") (pintype "passive"))
      (node (ref "JP4") (pin "11") (pinfunction "11_11") (pintype "passive"))
      (node (ref "JP4") (pin "12") (pinfunction "12_12") (pintype "passive"))
      (node (ref "JP4") (pin "13") (pinfunction "13_13") (pintype "passive"))
      (node (ref "JP4") (pin "14") (pinfunction "14_14") (pintype "passive"))
      (node (ref "JP4") (pin "15") (pinfunction "15_15") (pintype "passive"))
      (node (ref "JP4") (pin "16") (pinfunction "16_16") (pintype "passive"))
      (node (ref "JP4") (pin "17") (pinfunction "17_17") (pintype "passive"))
      (node (ref "JP4") (pin "18") (pinfunction "18_18") (pintype "passive"))
      (node (ref "JP4") (pin "19") (pinfunction "19_19") (pintype "passive"))
      (node (ref "JP4") (pin "21") (pinfunction "21_21") (pintype "passive"))
      (node (ref "JP4") (pin "23") (pinfunction "23_23") (pintype "passive"))
      (node (ref "JP4") (pin "25") (pinfunction "25_25") (pintype "passive"))
      (node (ref "JP4") (pin "3") (pinfunction "3_3") (pintype "passive"))
      (node (ref "JP4") (pin "31") (pinfunction "31_31") (pintype "passive"))
      (node (ref "JP4") (pin "33") (pinfunction "33_33") (pintype "passive"))
      (node (ref "JP4") (pin "35") (pinfunction "35_35") (pintype "passive"))
      (node (ref "JP4") (pin "5") (pinfunction "5_5") (pintype "passive"))
      (node (ref "JP4") (pin "9") (pinfunction "9_9") (pintype "passive"))
      (node (ref "Q3") (pin "2") (pinfunction "S_2") (pintype "passive"))
      (node (ref "QG1") (pin "7") (pinfunction "GND_7") (pintype "power_in"))
      (node (ref "U$1") (pin "9") (pinfunction "GND_9") (pintype "bidirectional"))
      (node (ref "U1") (pin "1") (pinfunction "VSS_1") (pintype "power_in"))
      (node (ref "U1") (pin "16") (pinfunction "DCD_16") (pintype "input"))
      (node (ref "U1") (pin "17") (pinfunction "DSR_17") (pintype "input"))
      (node (ref "X1") (pin "5") (pinfunction "5_5") (pintype "passive"))
    )
    (net (code "45") (name "IRQ") (class "Default")
      (node (ref "IC11") (pin "9") (pinfunction "IRQ_9") (pintype "open_collector"))
      (node (ref "SV1") (pin "30") (pinfunction "30_30") (pintype "passive"))
      (node (ref "U$1") (pin "1") (pinfunction "STD.P_1") (pintype "bidirectional"))
      (node (ref "U1") (pin "26") (pinfunction "IRQB_26") (pintype "output"))
    )
    (net (code "46") (name "KBD_CS") (class "Default")
      (node (ref "IC3") (pin "6") (pinfunction "CS_6") (pintype "input"))
      (node (ref "IC6") (pin "13") (pinfunction "Y2_13") (pintype "output"))
    )
    (net (code "47") (name "KCLK") (class "Default")
      (node (ref "C8") (pin "1") (pinfunction "1_1") (pintype "passive"))
      (node (ref "IC3") (pin "1") (pinfunction "T0_1") (pintype "input"))
      (node (ref "IC5") (pin "6") (pinfunction "O_6") (pintype "open_collector"))
      (node (ref "J1") (pin "1") (pinfunction "1_1") (pintype "bidirectional"))
      (node (ref "R7") (pin "1") (pinfunction "1_1") (pintype "passive"))
    )
    (net (code "48") (name "KDAT") (class "Default")
      (node (ref "C7") (pin "1") (pinfunction "1_1") (pintype "passive"))
      (node (ref "IC3") (pin "39") (pinfunction "T1_39") (pintype "input"))
      (node (ref "IC5") (pin "2") (pinfunction "O_2") (pintype "open_collector"))
      (node (ref "J1") (pin "2") (pinfunction "2_2") (pintype "bidirectional"))
      (node (ref "R8") (pin "1") (pinfunction "1_1") (pintype "passive"))
    )
    (net (code "49") (name "NMI") (class "Default")
      (node (ref "SV1") (pin "31") (pinfunction "31_31") (pintype "passive"))
    )
    (net (code "50") (name "Net-(BATTERY_1-Pad+)") (class "Default")
      (node (ref "BATTERY_1") (pin "+") (pinfunction "+_+") (pintype "bidirectional"))
      (node (ref "D1") (pin "A") (pinfunction "A_A") (pintype "passive"))
    )
    (net (code "51") (name "Net-(CON1A-{slash}CS1)") (class "Default")
      (node (ref "CON1") (pin "32") (pinfunction "/CS1_32") (pintype "input"))
      (node (ref "R2") (pin "1") (pinfunction "1_1") (pintype "passive"))
    )
    (net (code "52") (name "Net-(CON1A-{slash}PDIAG)") (class "Default")
      (node (ref "CON1") (pin "46") (pinfunction "/PDIAG_46") (pintype "bidirectional"))
      (node (ref "R5") (pin "1") (pinfunction "1_1") (pintype "passive"))
    )
    (net (code "53") (name "Net-(CON1A-{slash}REG)") (class "Default")
      (node (ref "CON1") (pin "44") (pinfunction "/REG_44") (pintype "input"))
      (node (ref "R4") (pin "1") (pinfunction "1_1") (pintype "passive"))
    )
    (net (code "54") (name "Net-(CON1A-{slash}WE)") (class "Default")
      (node (ref "CON1") (pin "36") (pinfunction "/WE_36") (pintype "input"))
      (node (ref "R3") (pin "1") (pinfunction "1_1") (pintype "passive"))
    )
    (net (code "55") (name "Net-(IC2A-C1+)") (class "Default")
      (node (ref "C4") (pin "2") (pinfunction "2_2") (pintype "passive"))
      (node (ref "IC2") (pin "1") (pinfunction "C1+_1") (pintype "bidirectional"))
    )
    (net (code "56") (name "Net-(IC2A-C1-)") (class "Default")
      (node (ref "C4") (pin "1") (pinfunction "1_1") (pintype "passive"))
      (node (ref "IC2") (pin "3") (pinfunction "C1-_3") (pintype "bidirectional"))
    )
    (net (code "57") (name "Net-(IC2A-C2+)") (class "Default")
      (node (ref "C5") (pin "2") (pinfunction "2_2") (pintype "passive"))
      (node (ref "IC2") (pin "4") (pinfunction "C2+_4") (pintype "bidirectional"))
    )
    (net (code "58") (name "Net-(IC2A-C2-)") (class "Default")
      (node (ref "C5") (pin "1") (pinfunction "1_1") (pintype "passive"))
      (node (ref "IC2") (pin "5") (pinfunction "C2-_5") (pintype "bidirectional"))
    )
    (net (code "59") (name "Net-(IC2A-R1IN)") (class "Default")
      (node (ref "IC2") (pin "13") (pinfunction "R1IN_13") (pintype "input"))
      (node (ref "X1") (pin "2") (pinfunction "2_2") (pintype "passive"))
    )
    (net (code "60") (name "Net-(IC2A-R1OUT)") (class "Default")
      (node (ref "IC2") (pin "12") (pinfunction "R1OUT_12") (pintype "output"))
      (node (ref "U1") (pin "12") (pinfunction "RXD_12") (pintype "input"))
    )
    (net (code "61") (name "Net-(IC2A-R2IN)") (class "Default")
      (node (ref "IC2") (pin "8") (pinfunction "R2IN_8") (pintype "input"))
      (node (ref "X1") (pin "8") (pinfunction "8_8") (pintype "passive"))
    )
    (net (code "62") (name "Net-(IC2A-R2OUT)") (class "Default")
      (node (ref "IC2") (pin "9") (pinfunction "R2OUT_9") (pintype "output"))
      (node (ref "U1") (pin "9") (pinfunction "CTS_9") (pintype "input"))
    )
    (net (code "63") (name "Net-(IC2A-T1IN)") (class "Default")
      (node (ref "IC2") (pin "11") (pinfunction "T1IN_11") (pintype "input"))
      (node (ref "U1") (pin "10") (pinfunction "TXD_10") (pintype "output"))
    )
    (net (code "64") (name "Net-(IC2A-T1OUT)") (class "Default")
      (node (ref "IC2") (pin "14") (pinfunction "T1OUT_14") (pintype "output"))
      (node (ref "X1") (pin "3") (pinfunction "3_3") (pintype "passive"))
    )
    (net (code "65") (name "Net-(IC2A-T2IN)") (class "Default")
      (node (ref "IC2") (pin "10") (pinfunction "T2IN_10") (pintype "input"))
      (node (ref "U1") (pin "8") (pinfunction "RTS_8") (pintype "output"))
    )
    (net (code "66") (name "Net-(IC2A-T2OUT)") (class "Default")
      (node (ref "IC2") (pin "7") (pinfunction "T2OUT_7") (pintype "output"))
      (node (ref "X1") (pin "7") (pinfunction "7_7") (pintype "passive"))
    )
    (net (code "67") (name "Net-(IC2A-V+)") (class "Default")
      (node (ref "C6") (pin "1") (pinfunction "1_1") (pintype "passive"))
      (node (ref "IC2") (pin "2") (pinfunction "V+_2") (pintype "bidirectional"))
    )
    (net (code "68") (name "Net-(IC2A-V-)") (class "Default")
      (node (ref "C24") (pin "1") (pinfunction "1_1") (pintype "passive"))
      (node (ref "IC2") (pin "6") (pinfunction "V-_6") (pintype "bidirectional"))
    )
    (net (code "69") (name "Net-(IC3-P26{slash}~{DRQ})") (class "Default")
      (node (ref "IC3") (pin "37") (pinfunction "P26/~{DRQ}_37") (pintype "bidirectional"))
      (node (ref "IC5") (pin "5") (pinfunction "I_5") (pintype "input"))
    )
    (net (code "70") (name "Net-(IC3-P27{slash}~{DAK})") (class "Default")
      (node (ref "IC3") (pin "38") (pinfunction "P27/~{DAK}_38") (pintype "bidirectional"))
      (node (ref "IC5") (pin "3") (pinfunction "I_3") (pintype "input"))
    )
    (net (code "71") (name "Net-(IC3-SS)") (class "Default")
      (node (ref "IC3") (pin "5") (pinfunction "SS_5") (pintype "input"))
      (node (ref "R19") (pin "1") (pinfunction "1_1") (pintype "passive"))
    )
    (net (code "72") (name "Net-(IC3-XTAL1)") (class "Default")
      (node (ref "C9") (pin "2") (pinfunction "2_2") (pintype "passive"))
      (node (ref "IC3") (pin "2") (pinfunction "XTAL1_2") (pintype "input"))
      (node (ref "Q2") (pin "2") (pinfunction "2_2") (pintype "passive"))
    )
    (net (code "73") (name "Net-(IC3-XTAL2)") (class "Default")
      (node (ref "C11") (pin "2") (pinfunction "2_2") (pintype "passive"))
      (node (ref "IC3") (pin "3") (pinfunction "XTAL2_3") (pintype "input"))
      (node (ref "Q2") (pin "1") (pinfunction "1_1") (pintype "passive"))
    )
    (net (code "74") (name "Net-(IC5A-I)") (class "Default")
      (node (ref "IC5") (pin "1") (pinfunction "I_1") (pintype "input"))
      (node (ref "IC5") (pin "4") (pinfunction "O_4") (pintype "open_collector"))
      (node (ref "R23") (pin "1") (pinfunction "1_1") (pintype "passive"))
    )
    (net (code "75") (name "Net-(IC6A-G1)") (class "Default")
      (node (ref "IC6") (pin "6") (pinfunction "G1_6") (pintype "input"))
      (node (ref "R9") (pin "1") (pinfunction "1_1") (pintype "passive"))
    )
    (net (code "76") (name "Net-(IC11A-C1)") (class "Default")
      (node (ref "IC11") (pin "28") (pinfunction "C1_28") (pintype "input"))
      (node (ref "R16") (pin "2") (pinfunction "2_2") (pintype "passive"))
    )
    (net (code "77") (name "Net-(IC11A-C2)") (class "Default")
      (node (ref "IC11") (pin "4") (pinfunction "C2_4") (pintype "input"))
      (node (ref "R17") (pin "2") (pinfunction "2_2") (pintype "passive"))
    )
    (net (code "78") (name "Net-(IC11A-C3)") (class "Default")
      (node (ref "IC11") (pin "7") (pinfunction "C3_7") (pintype "input"))
      (node (ref "R18") (pin "2") (pinfunction "2_2") (pintype "passive"))
    )
    (net (code "79") (name "Net-(IC11A-CS1)") (class "Default")
      (node (ref "IC11") (pin "16") (pinfunction "CS1_16") (pintype "input"))
      (node (ref "R15") (pin "1") (pinfunction "1_1") (pintype "passive"))
    )
    (net (code "80") (name "Net-(IC11A-O3)") (class "Default")
      (node (ref "IC11") (pin "6") (pinfunction "O3_6") (pintype "output"))
      (node (ref "R6") (pin "2") (pinfunction "2_2") (pintype "passive"))
    )
    (net (code "81") (name "Net-(J2-Pad3)") (class "Default")
      (node (ref "J2") (pin "3") (pinfunction "3_3") (pintype "bidirectional"))
      (node (ref "R20") (pin "1") (pinfunction "1_1") (pintype "passive"))
    )
    (net (code "82") (name "Net-(J2-Pad4)") (class "Default")
      (node (ref "J2") (pin "4") (pinfunction "4_4") (pintype "bidirectional"))
      (node (ref "R22") (pin "2") (pinfunction "2_2") (pintype "passive"))
    )
    (net (code "83") (name "Net-(J2-Pad5)") (class "Default")
      (node (ref "J2") (pin "5") (pinfunction "5_5") (pintype "bidirectional"))
      (node (ref "R21") (pin "1") (pinfunction "1_1") (pintype "passive"))
    )
    (net (code "84") (name "Net-(PAD1-P)") (class "Default")
      (node (ref "PAD1") (pin "1") (pinfunction "P_1") (pintype "passive"))
      (node (ref "Q3") (pin "3") (pinfunction "D_3") (pintype "passive"))
    )
    (net (code "85") (name "Net-(Q3-G)") (class "Default")
      (node (ref "Q3") (pin "1") (pinfunction "G_1") (pintype "passive"))
      (node (ref "R6") (pin "1") (pinfunction "1_1") (pintype "passive"))
    )
    (net (code "86") (name "Net-(QG1-TS)") (class "Default")
      (node (ref "QG1") (pin "1") (pinfunction "TS_1") (pintype "passive"))
      (node (ref "R1") (pin "1") (pinfunction "1_1") (pintype "passive"))
    )
    (net (code "87") (name "Net-(U$1-XT)") (class "Default")
      (node (ref "C23") (pin "2") (pinfunction "2_2") (pintype "passive"))
      (node (ref "U$1") (pin "16") (pinfunction "XT_16") (pintype "bidirectional"))
      (node (ref "X2") (pin "2") (pinfunction "2_2") (pintype "passive"))
    )
    (net (code "88") (name "Net-(U$1-~{XT})") (class "Default")
      (node (ref "C20") (pin "2") (pinfunction "2_2") (pintype "passive"))
      (node (ref "U$1") (pin "17") (pinfunction "~{XT}_17") (pintype "bidirectional"))
      (node (ref "X2") (pin "1") (pinfunction "1_1") (pintype "passive"))
    )
    (net (code "89") (name "Net-(U1-CS0)") (class "Default")
      (node (ref "R10") (pin "2") (pinfunction "2_2") (pintype "passive"))
      (node (ref "U1") (pin "2") (pinfunction "CS0_2") (pintype "input"))
    )
    (net (code "90") (name "OUT_1") (class "Default")
      (node (ref "SV1") (pin "1") (pinfunction "1_1") (pintype "passive"))
    )
    (net (code "91") (name "OUT_2") (class "Default")
      (node (ref "SV1") (pin "2") (pinfunction "2_2") (pintype "passive"))
    )
    (net (code "92") (name "OUT_3") (class "Default")
      (node (ref "SV1") (pin "3") (pinfunction "3_3") (pintype "passive"))
    )
    (net (code "93") (name "OUT_4") (class "Default")
      (node (ref "SV1") (pin "4") (pinfunction "4_4") (pintype "passive"))
    )
    (net (code "94") (name "PA0") (class "Default")
      (node (ref "IC4") (pin "4") (pinfunction "PA0_4") (pintype "bidirectional"))
      (node (ref "JP4") (pin "8") (pinfunction "8_8") (pintype "passive"))
    )
    (net (code "95") (name "PA1") (class "Default")
      (node (ref "IC4") (pin "3") (pinfunction "PA1_3") (pintype "bidirectional"))
      (node (ref "JP4") (pin "6") (pinfunction "6_6") (pintype "passive"))
    )
    (net (code "96") (name "PA2") (class "Default")
      (node (ref "IC4") (pin "2") (pinfunction "PA2_2") (pintype "bidirectional"))
      (node (ref "JP4") (pin "4") (pinfunction "4_4") (pintype "passive"))
    )
    (net (code "97") (name "PA3") (class "Default")
      (node (ref "IC4") (pin "1") (pinfunction "PA3_1") (pintype "bidirectional"))
      (node (ref "JP4") (pin "2") (pinfunction "2_2") (pintype "passive"))
    )
    (net (code "98") (name "PA7") (class "Default")
      (node (ref "IC4") (pin "37") (pinfunction "PA7_37") (pintype "bidirectional"))
      (node (ref "JP4") (pin "7") (pinfunction "7_7") (pintype "passive"))
    )
    (net (code "99") (name "PB0") (class "Default")
      (node (ref "IC4") (pin "18") (pinfunction "PB0_18") (pintype "bidirectional"))
      (node (ref "JP4") (pin "36") (pinfunction "36_36") (pintype "passive"))
    )
    (net (code "100") (name "PB1") (class "Default")
      (node (ref "IC4") (pin "19") (pinfunction "PB1_19") (pintype "bidirectional"))
      (node (ref "JP4") (pin "38") (pinfunction "38_38") (pintype "passive"))
    )
    (net (code "101") (name "PB2") (class "Default")
      (node (ref "IC4") (pin "20") (pinfunction "PB2_20") (pintype "bidirectional"))
      (node (ref "JP4") (pin "40") (pinfunction "40_40") (pintype "passive"))
    )
    (net (code "102") (name "PB3") (class "Default")
      (node (ref "IC4") (pin "21") (pinfunction "PB3_21") (pintype "bidirectional"))
      (node (ref "JP4") (pin "39") (pinfunction "39_39") (pintype "passive"))
    )
    (net (code "103") (name "PB4") (class "Default")
      (node (ref "IC4") (pin "22") (pinfunction "PB4_22") (pintype "bidirectional"))
      (node (ref "JP4") (pin "37") (pinfunction "37_37") (pintype "passive"))
    )
    (net (code "104") (name "PC0") (class "Default")
      (node (ref "IC4") (pin "14") (pinfunction "PC0_14") (pintype "bidirectional"))
      (node (ref "JP4") (pin "28") (pinfunction "28_28") (pintype "passive"))
    )
    (net (code "105") (name "PC1") (class "Default")
      (node (ref "IC4") (pin "15") (pinfunction "PC1_15") (pintype "bidirectional"))
      (node (ref "JP4") (pin "30") (pinfunction "30_30") (pintype "passive"))
    )
    (net (code "106") (name "PC2") (class "Default")
      (node (ref "IC4") (pin "16") (pinfunction "PC2_16") (pintype "bidirectional"))
      (node (ref "JP4") (pin "32") (pinfunction "32_32") (pintype "passive"))
    )
    (net (code "107") (name "PC3") (class "Default")
      (node (ref "IC4") (pin "17") (pinfunction "PC3_17") (pintype "bidirectional"))
      (node (ref "JP4") (pin "34") (pinfunction "34_34") (pintype "passive"))
    )
    (net (code "108") (name "PC4") (class "Default")
      (node (ref "IC4") (pin "13") (pinfunction "PC4_13") (pintype "bidirectional"))
      (node (ref "JP4") (pin "26") (pinfunction "26_26") (pintype "passive"))
    )
    (net (code "109") (name "PC5") (class "Default")
      (node (ref "IC4") (pin "12") (pinfunction "PC5_12") (pintype "bidirectional"))
      (node (ref "JP4") (pin "24") (pinfunction "24_24") (pintype "passive"))
    )
    (net (code "110") (name "PC6") (class "Default")
      (node (ref "IC4") (pin "11") (pinfunction "PC6_11") (pintype "bidirectional"))
      (node (ref "JP4") (pin "22") (pinfunction "22_22") (pintype "passive"))
    )
    (net (code "111") (name "PC7") (class "Default")
      (node (ref "IC4") (pin "10") (pinfunction "PC7_10") (pintype "bidirectional"))
      (node (ref "JP4") (pin "20") (pinfunction "20_20") (pintype "passive"))
    )
    (net (code "112") (name "RD") (class "Default")
      (node (ref "CON1") (pin "34") (pinfunction "/IORD_34") (pintype "input"))
      (node (ref "IC3") (pin "8") (pinfunction "RD_8") (pintype "input"))
      (node (ref "IC4") (pin "5") (pinfunction "RD_5") (pintype "input"))
      (node (ref "SV1") (pin "33") (pinfunction "33_33") (pintype "passive"))
      (node (ref "U$1") (pin "8") (pinfunction "~{RD}_8") (pintype "bidirectional"))
    )
    (net (code "113") (name "RST") (class "Default")
      (node (ref "CON1") (pin "41") (pinfunction "/RESET_41") (pintype "input"))
      (node (ref "IC1") (pin "9") (pinfunction "I_9") (pintype "input"))
      (node (ref "IC11") (pin "8") (pinfunction "RESET_8") (pintype "input"))
      (node (ref "IC3") (pin "4") (pinfunction "RESET_4") (pintype "input"))
      (node (ref "SV1") (pin "29") (pinfunction "29_29") (pintype "passive"))
      (node (ref "U1") (pin "4") (pinfunction "RESB_4") (pintype "input"))
    )
    (net (code "114") (name "RST_INV") (class "Default")
      (node (ref "IC1") (pin "8") (pinfunction "O_8") (pintype "open_collector"))
      (node (ref "IC4") (pin "35") (pinfunction "RESET_35") (pintype "input"))
      (node (ref "R11") (pin "1") (pinfunction "1_1") (pintype "passive"))
    )
    (net (code "115") (name "RTC_CS") (class "Default")
      (node (ref "IC6") (pin "12") (pinfunction "Y3_12") (pintype "output"))
      (node (ref "U$1") (pin "2") (pinfunction "~{CS0}_2") (pintype "bidirectional"))
    )
    (net (code "116") (name "RW") (class "Default")
      (node (ref "IC11") (pin "13") (pinfunction "R/~{W}_13") (pintype "input"))
      (node (ref "SV1") (pin "36") (pinfunction "36_36") (pintype "passive"))
      (node (ref "U1") (pin "28") (pinfunction "R/WB_28") (pintype "input"))
    )
    (net (code "117") (name "SRQ_IN") (class "Default")
      (node (ref "IC4") (pin "25") (pinfunction "PB7_25") (pintype "bidirectional"))
      (node (ref "J2") (pin "1") (pinfunction "1_1") (pintype "bidirectional"))
    )
    (net (code "118") (name "TIMER_CS") (class "Default")
      (node (ref "IC11") (pin "15") (pinfunction "CS0_15") (pintype "input"))
      (node (ref "IC6") (pin "14") (pinfunction "Y1_14") (pintype "output"))
    )
    (net (code "119") (name "UART_CLK") (class "Default")
      (node (ref "QG1") (pin "8") (pinfunction "OUT_8") (pintype "output"))
      (node (ref "U1") (pin "6") (pinfunction "XTL1_6") (pintype "input"))
    )
    (net (code "120") (name "UART_CS") (class "Default")
      (node (ref "IC6") (pin "15") (pinfunction "Y0_15") (pintype "output"))
      (node (ref "U1") (pin "3") (pinfunction "CS1B_3") (pintype "input"))
    )
    (net (code "121") (name "VCC") (class "Default")
      (node (ref "C1") (pin "1") (pinfunction "1_1") (pintype "passive"))
      (node (ref "C10") (pin "+") (pinfunction "+_+") (pintype "passive"))
      (node (ref "C12") (pin "2") (pinfunction "2_2") (pintype "passive"))
      (node (ref "C14") (pin "1") (pinfunction "1_1") (pintype "passive"))
      (node (ref "C15") (pin "1") (pinfunction "1_1") (pintype "passive"))
      (node (ref "C16") (pin "1") (pinfunction "1_1") (pintype "passive"))
      (node (ref "C17") (pin "1") (pinfunction "1_1") (pintype "passive"))
      (node (ref "C19") (pin "1") (pinfunction "1_1") (pintype "passive"))
      (node (ref "C2") (pin "1") (pinfunction "1_1") (pintype "passive"))
      (node (ref "C21") (pin "+") (pinfunction "+_+") (pintype "passive"))
      (node (ref "C22") (pin "2") (pinfunction "2_2") (pintype "passive"))
      (node (ref "C3") (pin "1") (pinfunction "1_1") (pintype "passive"))
      (node (ref "C6") (pin "2") (pinfunction "2_2") (pintype "passive"))
      (node (ref "CON1") (pin "13") (pinfunction "VCC2_13") (pintype "power_in"))
      (node (ref "CON1") (pin "38") (pinfunction "VCC1_38") (pintype "power_in"))
      (node (ref "D2") (pin "A") (pinfunction "A_A") (pintype "passive"))
      (node (ref "IC1") (pin "14") (pinfunction "VCC_14") (pintype "power_in"))
      (node (ref "IC11") (pin "14") (pinfunction "VCC_14") (pintype "power_in"))
      (node (ref "IC2") (pin "16") (pinfunction "VCC_16") (pintype "power_in"))
      (node (ref "IC3") (pin "25") (pinfunction "PROG_25") (pintype "bidirectional"))
      (node (ref "IC3") (pin "26") (pinfunction "VDD_26") (pintype "power_in"))
      (node (ref "IC3") (pin "40") (pinfunction "VCC_40") (pintype "power_in"))
      (node (ref "IC4") (pin "26") (pinfunction "VCC_26") (pintype "power_in"))
      (node (ref "IC5") (pin "14") (pinfunction "VCC_14") (pintype "power_in"))
      (node (ref "IC6") (pin "16") (pinfunction "VCC_16") (pintype "power_in"))
      (node (ref "J1") (pin "5") (pinfunction "5_5") (pintype "bidirectional"))
      (node (ref "JP3") (pin "2") (pinfunction "2_2") (pintype "passive"))
      (node (ref "PAD2") (pin "1") (pinfunction "P_1") (pintype "passive"))
      (node (ref "QG1") (pin "14") (pinfunction "VCC_14") (pintype "power_in"))
      (node (ref "R1") (pin "2") (pinfunction "2_2") (pintype "passive"))
      (node (ref "R10") (pin "1") (pinfunction "1_1") (pintype "passive"))
      (node (ref "R11") (pin "2") (pinfunction "2_2") (pintype "passive"))
      (node (ref "R12") (pin "2") (pinfunction "2_2") (pintype "passive"))
      (node (ref "R13") (pin "2") (pinfunction "2_2") (pintype "passive"))
      (node (ref "R14") (pin "2") (pinfunction "2_2") (pintype "passive"))
      (node (ref "R15") (pin "2") (pinfunction "2_2") (pintype "passive"))
      (node (ref "R16") (pin "1") (pinfunction "1_1") (pintype "passive"))
      (node (ref "R17") (pin "1") (pinfunction "1_1") (pintype "passive"))
      (node (ref "R18") (pin "1") (pinfunction "1_1") (pintype "passive"))
      (node (ref "R19") (pin "2") (pinfunction "2_2") (pintype "passive"))
      (node (ref "R2") (pin "2") (pinfunction "2_2") (pintype "passive"))
      (node (ref "R23") (pin "2") (pinfunction "2_2") (pintype "passive"))
      (node (ref "R3") (pin "2") (pinfunction "2_2") (pintype "passive"))
      (node (ref "R4") (pin "2") (pinfunction "2_2") (pintype "passive"))
      (node (ref "R5") (pin "2") (pinfunction "2_2") (pintype "passive"))
      (node (ref "R7") (pin "2") (pinfunction "2_2") (pintype "passive"))
      (node (ref "R8") (pin "2") (pinfunction "2_2") (pintype "passive"))
      (node (ref "R9") (pin "2") (pinfunction "2_2") (pintype "passive"))
      (node (ref "U$1") (pin "15") (pinfunction "CS1_15") (pintype "bidirectional"))
      (node (ref "U$1") (pin "3") (pinfunction "ALE_3") (pintype "bidirectional"))
      (node (ref "U1") (pin "15") (pinfunction "VDD_15") (pintype "power_in"))
    )
    (net (code "122") (name "VPA") (class "Default")
      (node (ref "C13") (pin "2") (pinfunction "2_2") (pintype "passive"))
      (node (ref "C18") (pin "+") (pinfunction "+_+") (pintype "passive"))
      (node (ref "D1") (pin "C") (pinfunction "C_C") (pintype "passive"))
      (node (ref "D2") (pin "C") (pinfunction "C_C") (pintype "passive"))
      (node (ref "U$1") (pin "18") (pinfunction "VDD_18") (pintype "bidirectional"))
    )
    (net (code "123") (name "WR") (class "Default")
      (node (ref "CON1") (pin "35") (pinfunction "/IOWR_35") (pintype "input"))
      (node (ref "IC3") (pin "10") (pinfunction "WR_10") (pintype "input"))
      (node (ref "IC4") (pin "36") (pinfunction "WR_36") (pintype "input"))
      (node (ref "SV1") (pin "34") (pinfunction "34_34") (pintype "passive"))
      (node (ref "U$1") (pin "10") (pinfunction "~{WR}_10") (pintype "bidirectional"))
    )
    (net (code "124") (name "unconnected-(CON1A-D08-Pad47)") (class "Default")
      (node (ref "CON1") (pin "47") (pinfunction "D08_47") (pintype "bidirectional"))
    )
    (net (code "125") (name "unconnected-(CON1A-D09-Pad48)") (class "Default")
      (node (ref "CON1") (pin "48") (pinfunction "D09_48") (pintype "bidirectional"))
    )
    (net (code "126") (name "unconnected-(CON1A-D10-Pad49)") (class "Default")
      (node (ref "CON1") (pin "49") (pinfunction "D10_49") (pintype "bidirectional"))
    )
    (net (code "127") (name "unconnected-(CON1A-D11-Pad27)") (class "Default")
      (node (ref "CON1") (pin "27") (pinfunction "D11_27") (pintype "bidirectional"))
    )
    (net (code "128") (name "unconnected-(CON1A-D12-Pad28)") (class "Default")
      (node (ref "CON1") (pin "28") (pinfunction "D12_28") (pintype "bidirectional"))
    )
    (net (code "129") (name "unconnected-(CON1A-D13-Pad29)") (class "Default")
      (node (ref "CON1") (pin "29") (pinfunction "D13_29") (pintype "bidirectional"))
    )
    (net (code "130") (name "unconnected-(CON1A-D14-Pad30)") (class "Default")
      (node (ref "CON1") (pin "30") (pinfunction "D14_30") (pintype "bidirectional"))
    )
    (net (code "131") (name "unconnected-(CON1A-D15-Pad31)") (class "Default")
      (node (ref "CON1") (pin "31") (pinfunction "D15_31") (pintype "bidirectional"))
    )
    (net (code "132") (name "unconnected-(CON1A-INTRQ-Pad37)") (class "Default")
      (node (ref "CON1") (pin "37") (pinfunction "INTRQ_37") (pintype "output"))
    )
    (net (code "133") (name "unconnected-(CON1A-IORDY-Pad42)") (class "Default")
      (node (ref "CON1") (pin "42") (pinfunction "IORDY_42") (pintype "output"))
    )
    (net (code "134") (name "unconnected-(CON1A-{slash}CD1-Pad26)") (class "Default")
      (node (ref "CON1") (pin "26") (pinfunction "/CD1_26") (pintype "output"))
    )
    (net (code "135") (name "unconnected-(CON1A-{slash}CD2-Pad25)") (class "Default")
      (node (ref "CON1") (pin "25") (pinfunction "/CD2_25") (pintype "output"))
    )
    (net (code "136") (name "unconnected-(CON1A-{slash}DASP-Pad45)") (class "Default")
      (node (ref "CON1") (pin "45") (pinfunction "/DASP_45") (pintype "bidirectional"))
    )
    (net (code "137") (name "unconnected-(CON1A-{slash}INPACK-Pad43)") (class "Default")
      (node (ref "CON1") (pin "43") (pinfunction "/INPACK_43") (pintype "output"))
    )
    (net (code "138") (name "unconnected-(CON1A-{slash}IOCS16-Pad24)") (class "Default")
      (node (ref "CON1") (pin "24") (pinfunction "/IOCS16_24") (pintype "output"))
    )
    (net (code "139") (name "unconnected-(CON1A-{slash}VS1-Pad33)") (class "Default")
      (node (ref "CON1") (pin "33") (pinfunction "/VS1_33") (pintype "output"))
    )
    (net (code "140") (name "unconnected-(CON1A-{slash}VS2-Pad40)") (class "Default")
      (node (ref "CON1") (pin "40") (pinfunction "/VS2_40") (pintype "output"))
    )
    (net (code "141") (name "unconnected-(IC1E-O-Pad10)") (class "Default")
      (node (ref "IC1") (pin "10") (pinfunction "O_10") (pintype "open_collector"))
    )
    (net (code "142") (name "unconnected-(IC1F-O-Pad12)") (class "Default")
      (node (ref "IC1") (pin "12") (pinfunction "O_12") (pintype "open_collector"))
    )
    (net (code "143") (name "unconnected-(IC3-P11-Pad28)") (class "Default")
      (node (ref "IC3") (pin "28") (pinfunction "P11_28") (pintype "bidirectional"))
    )
    (net (code "144") (name "unconnected-(IC3-P12-Pad29)") (class "Default")
      (node (ref "IC3") (pin "29") (pinfunction "P12_29") (pintype "bidirectional"))
    )
    (net (code "145") (name "unconnected-(IC3-P13-Pad30)") (class "Default")
      (node (ref "IC3") (pin "30") (pinfunction "P13_30") (pintype "bidirectional"))
    )
    (net (code "146") (name "unconnected-(IC3-P14-Pad31)") (class "Default")
      (node (ref "IC3") (pin "31") (pinfunction "P14_31") (pintype "bidirectional"))
    )
    (net (code "147") (name "unconnected-(IC3-P15-Pad32)") (class "Default")
      (node (ref "IC3") (pin "32") (pinfunction "P15_32") (pintype "bidirectional"))
    )
    (net (code "148") (name "unconnected-(IC3-P16-Pad33)") (class "Default")
      (node (ref "IC3") (pin "33") (pinfunction "P16_33") (pintype "bidirectional"))
    )
    (net (code "149") (name "unconnected-(IC3-P17-Pad34)") (class "Default")
      (node (ref "IC3") (pin "34") (pinfunction "P17_34") (pintype "bidirectional"))
    )
    (net (code "150") (name "unconnected-(IC3-P24{slash}OBF-Pad35)") (class "Default")
      (node (ref "IC3") (pin "35") (pinfunction "P24/OBF_35") (pintype "bidirectional"))
    )
    (net (code "151") (name "unconnected-(IC3-P25{slash}~{IBF}-Pad36)") (class "Default")
      (node (ref "IC3") (pin "36") (pinfunction "P25/~{IBF}_36") (pintype "bidirectional"))
    )
    (net (code "152") (name "unconnected-(IC3-SYNC-Pad11)") (class "Default")
      (node (ref "IC3") (pin "11") (pinfunction "SYNC_11") (pintype "output"))
    )
    (net (code "153") (name "unconnected-(IC5D-O-Pad8)") (class "Default")
      (node (ref "IC5") (pin "8") (pinfunction "O_8") (pintype "open_collector"))
    )
    (net (code "154") (name "unconnected-(IC5E-O-Pad10)") (class "Default")
      (node (ref "IC5") (pin "10") (pinfunction "O_10") (pintype "open_collector"))
    )
    (net (code "155") (name "unconnected-(IC5F-O-Pad12)") (class "Default")
      (node (ref "IC5") (pin "12") (pinfunction "O_12") (pintype "open_collector"))
    )
    (net (code "156") (name "unconnected-(IC6A-Y6-Pad9)") (class "Default")
      (node (ref "IC6") (pin "9") (pinfunction "Y6_9") (pintype "output"))
    )
    (net (code "157") (name "unconnected-(IC6A-Y7-Pad7)") (class "Default")
      (node (ref "IC6") (pin "7") (pinfunction "Y7_7") (pintype "output"))
    )
    (net (code "158") (name "unconnected-(IC11A-O1-Pad27)") (class "Default")
      (node (ref "IC11") (pin "27") (pinfunction "O1_27") (pintype "output"))
    )
    (net (code "159") (name "unconnected-(IC11A-O2-Pad3)") (class "Default")
      (node (ref "IC11") (pin "3") (pinfunction "O2_3") (pintype "output"))
    )
    (net (code "160") (name "unconnected-(J1-Pad3)") (class "Default")
      (node (ref "J1") (pin "3") (pinfunction "3_3") (pintype "bidirectional"))
    )
    (net (code "161") (name "unconnected-(U1-DTR-Pad11)") (class "Default")
      (node (ref "U1") (pin "11") (pinfunction "DTR_11") (pintype "output"))
    )
    (net (code "162") (name "unconnected-(U1-RXCLK-Pad5)") (class "Default")
      (node (ref "U1") (pin "5") (pinfunction "RXCLK_5") (pintype "bidirectional"))
    )
    (net (code "163") (name "unconnected-(U1-XTL2-Pad7)") (class "Default")
      (node (ref "U1") (pin "7") (pinfunction "XTL2_7") (pintype "output"))
    )
    (net (code "164") (name "unconnected-(X1-Pad1)") (class "Default")
      (node (ref "X1") (pin "1") (pinfunction "1_1") (pintype "passive"))
    )
    (net (code "165") (name "unconnected-(X1-Pad4)") (class "Default")
      (node (ref "X1") (pin "4") (pinfunction "4_4") (pintype "passive"))
    )
    (net (code "166") (name "unconnected-(X1-Pad6)") (class "Default")
      (node (ref "X1") (pin "6") (pinfunction "6_6") (pintype "passive"))
    )
    (net (code "167") (name "unconnected-(X1-Pad9)") (class "Default")
      (node (ref "X1") (pin "9") (pinfunction "9_9") (pintype "passive"))
    )
  )
)
